# Master_1.net
KiCad netlist of a schematic drawn in Altium Designer
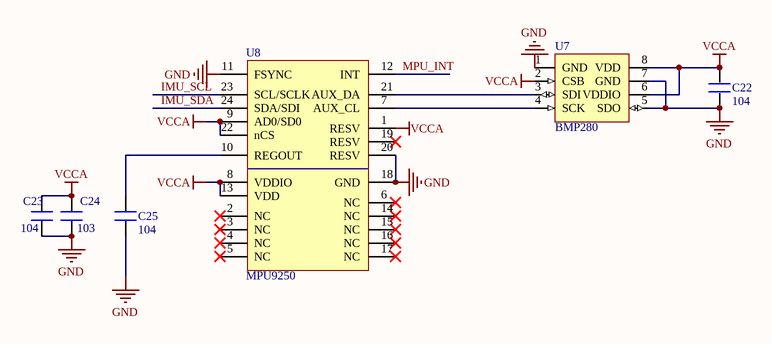
[diagram p0: Master_1.SchDoc]

(export (version "E")
  (design (tool "Eeschema 10.0.6"))
  (components
    (comp (ref "C22") (value "104") (footprint "0402") (libsource (lib "MiniFly ") (part "C")))
    (comp (ref "C23") (value "104") (footprint "0402") (libsource (lib "MiniFly ") (part "C")))
    (comp (ref "C24") (value "103") (footprint "0402") (libsource (lib "MiniFly ") (part "C")))
    (comp (ref "C25") (value "104") (footprint "0402") (libsource (lib "MiniFly ") (part "C")))
    (comp (ref "U7") (value "BMP280") (footprint "LGA-8") (libsource (lib "MiniFly ") (part "BMP280")))
    (comp (ref "U8") (value "MPU9250") (footprint "QFN24-0.4") (libsource (lib "MiniFly ") (part "MPU9250")))
  )
  (nets
    (net (code "1") (name "/IMU_SCL") (class "Default")
      (node (ref "U8") (pin "23") (pinfunction "SCL/SCLK_23") (pintype "passive"))
    )
    (net (code "2") (name "/IMU_SDA") (class "Default")
      (node (ref "U8") (pin "24") (pinfunction "SDA/SDI_24") (pintype "passive"))
    )
    (net (code "3") (name "/MPU_INT") (class "Default")
      (node (ref "U8") (pin "12") (pinfunction "INT_12") (pintype "passive"))
    )
    (net (code "4") (name "GND") (class "Default")
      (node (ref "C22") (pin "1") (pintype "passive"))
      (node (ref "C23") (pin "1") (pintype "passive"))
      (node (ref "C24") (pin "1") (pintype "passive"))
      (node (ref "C25") (pin "1") (pintype "passive"))
      (node (ref "U7") (pin "1") (pinfunction "GND_1") (pintype "passive"))
      (node (ref "U7") (pin "5") (pinfunction "SDO_5") (pintype "bidirectional"))
      (node (ref "U7") (pin "7") (pinfunction "GND_7") (pintype "power_in"))
      (node (ref "U8") (pin "11") (pinfunction "FSYNC_11") (pintype "passive"))
      (node (ref "U8") (pin "18") (pinfunction "GND_18") (pintype "passive"))
      (node (ref "U8") (pin "20") (pinfunction "RESV_20") (pintype "passive"))
    )
    (net (code "5") (name "Net-(U7-SCK)") (class "Default")
      (node (ref "U7") (pin "4") (pinfunction "SCK_4") (pintype "input"))
      (node (ref "U8") (pin "7") (pinfunction "AUX_CL_7") (pintype "passive"))
    )
    (net (code "6") (name "Net-(U7-SDI)") (class "Default")
      (node (ref "U7") (pin "3") (pinfunction "SDI_3") (pintype "bidirectional"))
      (node (ref "U8") (pin "21") (pinfunction "AUX_DA_21") (pintype "passive"))
    )
    (net (code "7") (name "Net-(U8-REGOUT)") (class "Default")
      (node (ref "C25") (pin "2") (pintype "passive"))
      (node (ref "U8") (pin "10") (pinfunction "REGOUT_10") (pintype "passive"))
    )
    (net (code "8") (name "VCCA") (class "Default")
      (node (ref "C22") (pin "2") (pintype "passive"))
      (node (ref "C23") (pin "2") (pintype "passive"))
      (node (ref "C24") (pin "2") (pintype "passive"))
      (node (ref "U7") (pin "2") (pinfunction "CSB_2") (pintype "input"))
      (node (ref "U7") (pin "6") (pinfunction "VDDIO_6") (pintype "power_in"))
      (node (ref "U7") (pin "8") (pinfunction "VDD_8") (pintype "power_in"))
      (node (ref "U8") (pin "1") (pinfunction "RESV_1") (pintype "passive"))
      (node (ref "U8") (pin "13") (pinfunction "VDD_13") (pintype "passive"))
      (node (ref "U8") (pin "22") (pinfunction "nCS_22") (pintype "passive"))
      (node (ref "U8") (pin "8") (pinfunction "VDDIO_8") (pintype "passive"))
      (node (ref "U8") (pin "9") (pinfunction "AD0/SD0_9") (pintype "passive"))
    )
    (net (code "9") (name "unconnected-(U8-NC-Pad2)") (class "Default")
      (node (ref "U8") (pin "2") (pinfunction "NC_2") (pintype "passive+no_connect"))
    )
    (net (code "10") (name "unconnected-(U8-NC-Pad3)") (class "Default")
      (node (ref "U8") (pin "3") (pinfunction "NC_3") (pintype "passive+no_connect"))
    )
    (net (code "11") (name "unconnected-(U8-NC-Pad4)") (class "Default")
      (node (ref "U8") (pin "4") (pinfunction "NC_4") (pintype "passive+no_connect"))
    )
    (net (code "12") (name "unconnected-(U8-NC-Pad5)") (class "Default")
      (node (ref "U8") (pin "5") (pinfunction "NC_5") (pintype "passive+no_connect"))
    )
    (net (code "13") (name "unconnected-(U8-NC-Pad6)") (class "Default")
      (node (ref "U8") (pin "6") (pinfunction "NC_6") (pintype "passive+no_connect"))
    )
    (net (code "14") (name "unconnected-(U8-NC-Pad14)") (class "Default")
      (node (ref "U8") (pin "14") (pinfunction "NC_14") (pintype "passive+no_connect"))
    )
    (net (code "15") (name "unconnected-(U8-NC-Pad15)") (class "Default")
      (node (ref "U8") (pin "15") (pinfunction "NC_15") (pintype "passive+no_connect"))
    )
    (net (code "16") (name "unconnected-(U8-NC-Pad16)") (class "Default")
      (node (ref "U8") (pin "16") (pinfunction "NC_16") (pintype "passive+no_connect"))
    )
    (net (code "17") (name "unconnected-(U8-NC-Pad17)") (class "Default")
      (node (ref "U8") (pin "17") (pinfunction "NC_17") (pintype "passive+no_connect"))
    )
    (net (code "18") (name "unconnected-(U8-RESV-Pad19)") (class "Default")
      (node (ref "U8") (pin "19") (pinfunction "RESV_19") (pintype "passive+no_connect"))
    )
  )
)
